# Digital_Inputs.net
KiCad netlist of a schematic drawn in Altium Designer
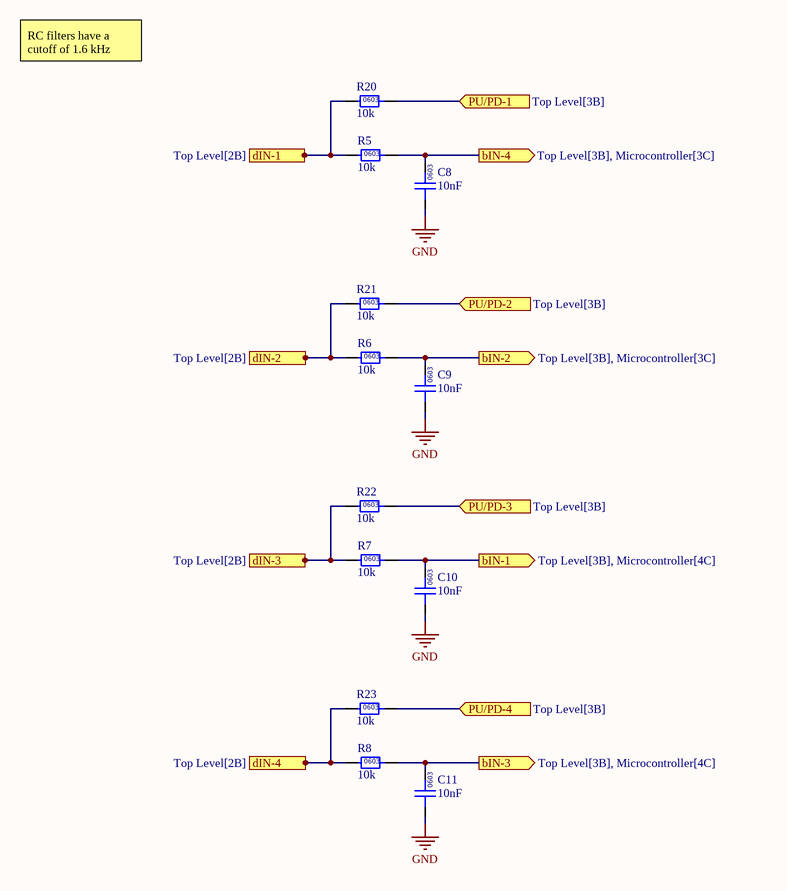
[diagram p0: Digital_Inputs.SchDoc]

(export (version "E")
  (design (tool "Eeschema 10.0.6"))
  (components
    (comp (ref "C8")
      (value "10nF")
      (footprint "0603")
      (fields
        (field (name "PART NUMBER") "GCM188L81H103KA03D")
        (field (name "MANUFACTURER") "muRata")
        (field (name "TOLERANCE") "±10%")
      )
      (libsource (lib "ts_standard_library") (part "Capacitor 0603"))
    )
    (comp (ref "C9")
      (value "10nF")
      (footprint "0603")
      (fields
        (field (name "PART NUMBER") "GCM188L81H103KA03D")
        (field (name "MANUFACTURER") "muRata")
        (field (name "TOLERANCE") "±10%")
      )
      (libsource (lib "ts_standard_library") (part "Capacitor 0603"))
    )
    (comp (ref "C10")
      (value "10nF")
      (footprint "0603")
      (fields
        (field (name "PART NUMBER") "GCM188L81H103KA03D")
        (field (name "MANUFACTURER") "muRata")
        (field (name "TOLERANCE") "±10%")
      )
      (libsource (lib "ts_standard_library") (part "Capacitor 0603"))
    )
    (comp (ref "C11")
      (value "10nF")
      (footprint "0603")
      (fields
        (field (name "PART NUMBER") "GCM188L81H103KA03D")
        (field (name "MANUFACTURER") "muRata")
        (field (name "TOLERANCE") "±10%")
      )
      (libsource (lib "ts_standard_library") (part "Capacitor 0603"))
    )
    (comp (ref "R5")
      (value "10k")
      (footprint "0603")
      (fields
        (field (name "PART NUMBER") "RC0603FR-0710KL")
        (field (name "MANUFACTURER") "YAGEO")
        (field (name "TOLERANCE") "0.01")
      )
      (libsource (lib "ts_standard_library") (part "Resistor 0603"))
    )
    (comp (ref "R6")
      (value "10k")
      (footprint "0603")
      (fields
        (field (name "PART NUMBER") "RC0603FR-0710KL")
        (field (name "MANUFACTURER") "YAGEO")
        (field (name "TOLERANCE") "0.01")
      )
      (libsource (lib "ts_standard_library") (part "Resistor 0603"))
    )
    (comp (ref "R7")
      (value "10k")
      (footprint "0603")
      (fields
        (field (name "PART NUMBER") "RC0603FR-0710KL")
        (field (name "MANUFACTURER") "YAGEO")
        (field (name "TOLERANCE") "0.01")
      )
      (libsource (lib "ts_standard_library") (part "Resistor 0603"))
    )
    (comp (ref "R8")
      (value "10k")
      (footprint "0603")
      (fields
        (field (name "PART NUMBER") "RC0603FR-0710KL")
        (field (name "MANUFACTURER") "YAGEO")
        (field (name "TOLERANCE") "0.01")
      )
      (libsource (lib "ts_standard_library") (part "Resistor 0603"))
    )
    (comp (ref "R20")
      (value "10k")
      (footprint "0603")
      (fields
        (field (name "PART NUMBER") "RC0603FR-0710KL")
        (field (name "MANUFACTURER") "YAGEO")
        (field (name "TOLERANCE") "0.01")
      )
      (libsource (lib "ts_standard_library") (part "Resistor 0603"))
    )
    (comp (ref "R21")
      (value "10k")
      (footprint "0603")
      (fields
        (field (name "PART NUMBER") "RC0603FR-0710KL")
        (field (name "MANUFACTURER") "YAGEO")
        (field (name "TOLERANCE") "0.01")
      )
      (libsource (lib "ts_standard_library") (part "Resistor 0603"))
    )
    (comp (ref "R22")
      (value "10k")
      (footprint "0603")
      (fields
        (field (name "PART NUMBER") "RC0603FR-0710KL")
        (field (name "MANUFACTURER") "YAGEO")
        (field (name "TOLERANCE") "0.01")
      )
      (libsource (lib "ts_standard_library") (part "Resistor 0603"))
    )
    (comp (ref "R23")
      (value "10k")
      (footprint "0603")
      (fields
        (field (name "PART NUMBER") "RC0603FR-0710KL")
        (field (name "MANUFACTURER") "YAGEO")
        (field (name "TOLERANCE") "0.01")
      )
      (libsource (lib "ts_standard_library") (part "Resistor 0603"))
    )
  )
  (nets
    (net (code "1") (name "/PU{slash}PD-1") (class "Default")
      (node (ref "R20") (pin "2") (pinfunction "2_2") (pintype "passive"))
    )
    (net (code "2") (name "/PU{slash}PD-2") (class "Default")
      (node (ref "R21") (pin "2") (pinfunction "2_2") (pintype "passive"))
    )
    (net (code "3") (name "/PU{slash}PD-3") (class "Default")
      (node (ref "R22") (pin "2") (pinfunction "2_2") (pintype "passive"))
    )
    (net (code "4") (name "/PU{slash}PD-4") (class "Default")
      (node (ref "R23") (pin "2") (pinfunction "2_2") (pintype "passive"))
    )
    (net (code "5") (name "/bIN-1") (class "Default")
      (node (ref "C10") (pin "2") (pinfunction "2_2") (pintype "passive"))
      (node (ref "R7") (pin "2") (pinfunction "2_2") (pintype "passive"))
    )
    (net (code "6") (name "/bIN-2") (class "Default")
      (node (ref "C9") (pin "2") (pinfunction "2_2") (pintype "passive"))
      (node (ref "R6") (pin "2") (pinfunction "2_2") (pintype "passive"))
    )
    (net (code "7") (name "/bIN-3") (class "Default")
      (node (ref "C11") (pin "2") (pinfunction "2_2") (pintype "passive"))
      (node (ref "R8") (pin "2") (pinfunction "2_2") (pintype "passive"))
    )
    (net (code "8") (name "/bIN-4") (class "Default")
      (node (ref "C8") (pin "2") (pinfunction "2_2") (pintype "passive"))
      (node (ref "R5") (pin "2") (pinfunction "2_2") (pintype "passive"))
    )
    (net (code "9") (name "/dIN-1") (class "Default")
      (node (ref "R20") (pin "1") (pinfunction "1_1") (pintype "passive"))
      (node (ref "R5") (pin "1") (pinfunction "1_1") (pintype "passive"))
    )
    (net (code "10") (name "/dIN-2") (class "Default")
      (node (ref "R21") (pin "1") (pinfunction "1_1") (pintype "passive"))
      (node (ref "R6") (pin "1") (pinfunction "1_1") (pintype "passive"))
    )
    (net (code "11") (name "/dIN-3") (class "Default")
      (node (ref "R22") (pin "1") (pinfunction "1_1") (pintype "passive"))
      (node (ref "R7") (pin "1") (pinfunction "1_1") (pintype "passive"))
    )
    (net (code "12") (name "/dIN-4") (class "Default")
      (node (ref "R23") (pin "1") (pinfunction "1_1") (pintype "passive"))
      (node (ref "R8") (pin "1") (pinfunction "1_1") (pintype "passive"))
    )
    (net (code "13") (name "GND") (class "Default")
      (node (ref "C10") (pin "1") (pinfunction "1_1") (pintype "passive"))
      (node (ref "C11") (pin "1") (pinfunction "1_1") (pintype "passive"))
      (node (ref "C8") (pin "1") (pinfunction "1_1") (pintype "passive"))
      (node (ref "C9") (pin "1") (pinfunction "1_1") (pintype "passive"))
    )
  )
)
